# 01_-_ST-LINK_V2_1.net
KiCad netlist of a schematic drawn in Altium Designer
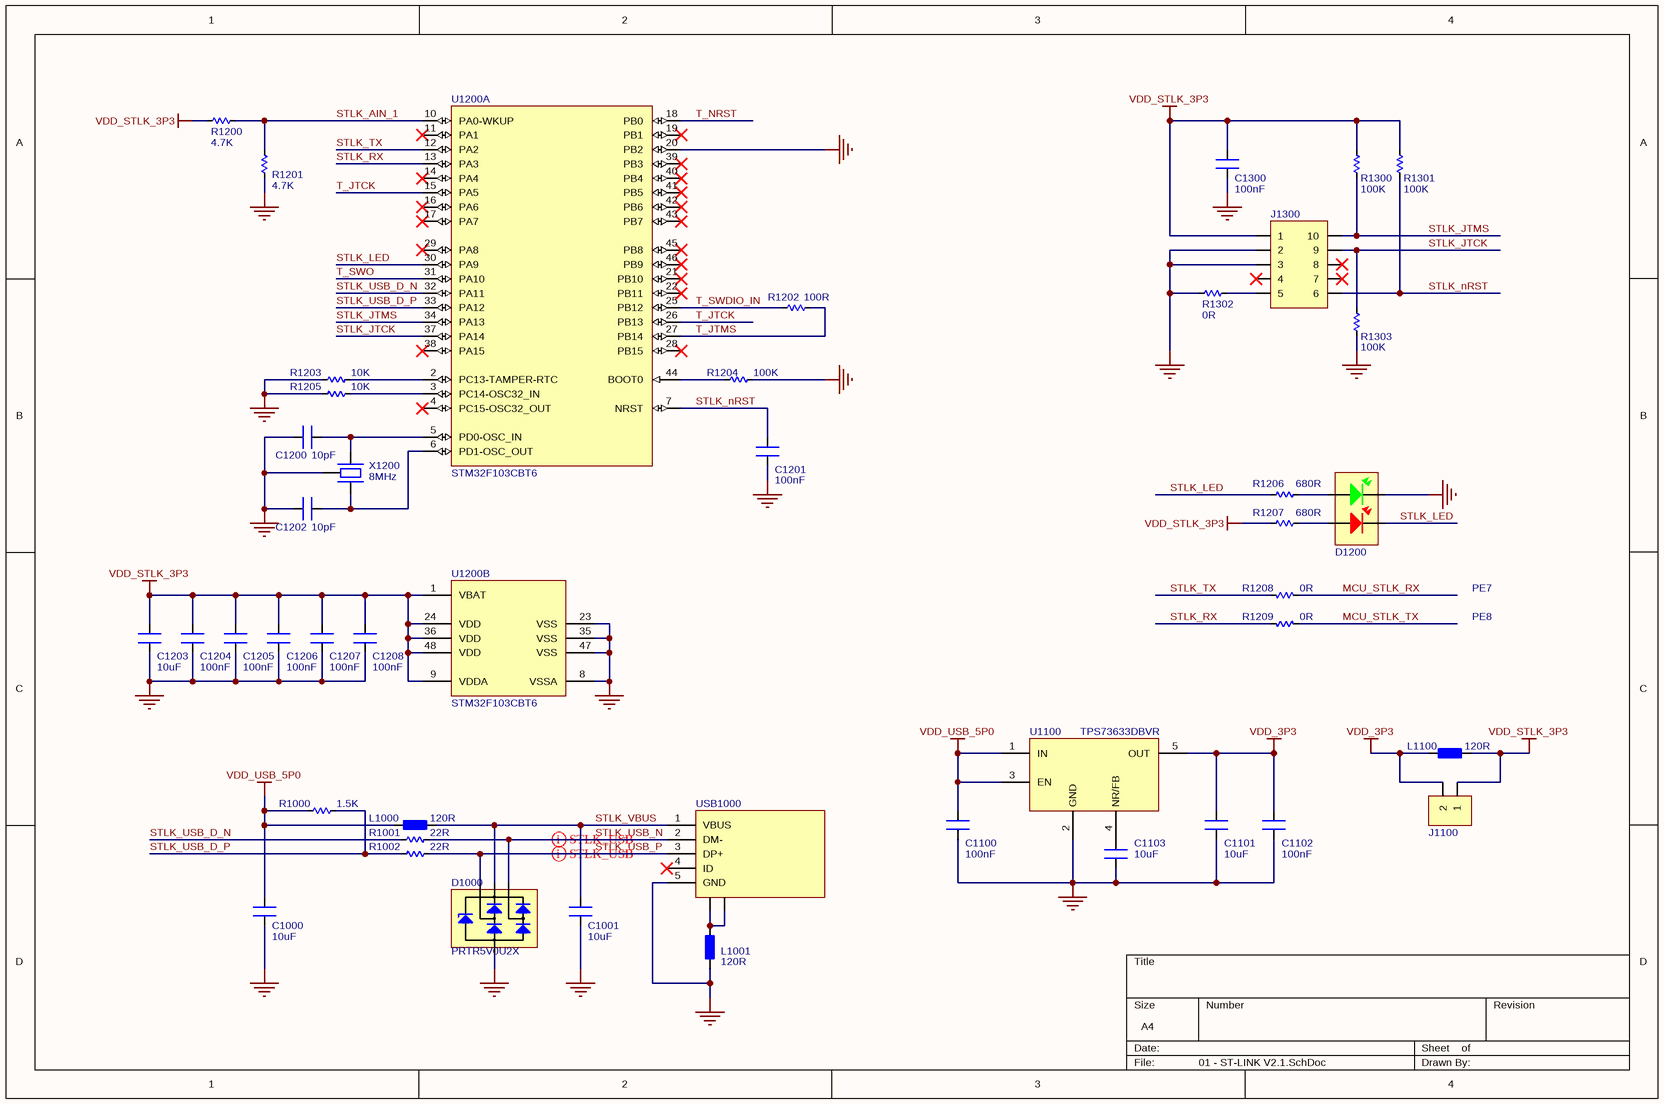
[diagram p0: 01 - ST-LINK V2.1.SchDoc]

(export (version "E")
  (design (tool "Eeschema 10.0.6"))
  (components
    (comp (ref "C1000")
      (value "10uF")
      (footprint "CN-SMD-0603")
      (description "Ceramic Capacitor SMD 0603 10uF ±20% 10V")
      (fields (field (name "Comment") "Capacitor"))
      (libsource (lib "AS50") (part "Cap"))
    )
    (comp (ref "C1001")
      (value "10uF")
      (footprint "CN-SMD-0603")
      (description "Ceramic Capacitor SMD 0603 10uF ±20% 10V")
      (fields (field (name "Comment") "Capacitor"))
      (libsource (lib "AS50") (part "Cap"))
    )
    (comp (ref "C1100")
      (value "100nF")
      (footprint "CN-SMD-0603")
      (description "Ceramic Capacitor SMD 0603 100nF ±20% 50V")
      (fields (field (name "Comment") "Capacitor"))
      (libsource (lib "AS50") (part "Cap"))
    )
    (comp (ref "C1101")
      (value "10uF")
      (footprint "CN-SMD-0603")
      (description "Ceramic Capacitor SMD 0603 10uF ±20% 10V")
      (fields (field (name "Comment") "Capacitor"))
      (libsource (lib "AS50") (part "Cap"))
    )
    (comp (ref "C1102")
      (value "100nF")
      (footprint "CN-SMD-0603")
      (description "Ceramic Capacitor SMD 0603 100nF ±20% 50V")
      (fields (field (name "Comment") "Capacitor"))
      (libsource (lib "AS50") (part "Cap"))
    )
    (comp (ref "C1103")
      (value "10uF")
      (footprint "CN-SMD-0603")
      (description "Ceramic Capacitor SMD 0603 10uF ±20% 10V")
      (fields (field (name "Comment") "Capacitor"))
      (libsource (lib "AS50") (part "Cap"))
    )
    (comp (ref "C1200")
      (value "10pF")
      (footprint "CN-SMD-0402")
      (description "Ceramic Capacitor SMD 0402 10pF ±20% 50V")
      (fields (field (name "Comment") "Capacitor"))
      (libsource (lib "AS50") (part "Cap"))
    )
    (comp (ref "C1201")
      (value "100nF")
      (footprint "CN-SMD-0402")
      (description "Ceramic Capacitor SMD 0402 100nF ±20% 16V")
      (fields (field (name "Comment") "Capacitor"))
      (libsource (lib "AS50") (part "Cap"))
    )
    (comp (ref "C1202")
      (value "10pF")
      (footprint "CN-SMD-0402")
      (description "Ceramic Capacitor SMD 0402 10pF ±20% 50V")
      (fields (field (name "Comment") "Capacitor"))
      (libsource (lib "AS50") (part "Cap"))
    )
    (comp (ref "C1203")
      (value "10uF")
      (footprint "CN-SMD-0603")
      (description "Ceramic Capacitor SMD 0603 10uF ±20% 10V")
      (fields (field (name "Comment") "Capacitor"))
      (libsource (lib "AS50") (part "Cap"))
    )
    (comp (ref "C1204")
      (value "100nF")
      (footprint "CN-SMD-0402")
      (description "Ceramic Capacitor SMD 0402 100nF ±20% 16V")
      (fields (field (name "Comment") "Capacitor"))
      (libsource (lib "AS50") (part "Cap"))
    )
    (comp (ref "C1205")
      (value "100nF")
      (footprint "CN-SMD-0402")
      (description "Ceramic Capacitor SMD 0402 100nF ±20% 16V")
      (fields (field (name "Comment") "Capacitor"))
      (libsource (lib "AS50") (part "Cap"))
    )
    (comp (ref "C1206")
      (value "100nF")
      (footprint "CN-SMD-0402")
      (description "Ceramic Capacitor SMD 0402 100nF ±20% 16V")
      (fields (field (name "Comment") "Capacitor"))
      (libsource (lib "AS50") (part "Cap"))
    )
    (comp (ref "C1207")
      (value "100nF")
      (footprint "CN-SMD-0402")
      (description "Ceramic Capacitor SMD 0402 100nF ±20% 16V")
      (fields (field (name "Comment") "Capacitor"))
      (libsource (lib "AS50") (part "Cap"))
    )
    (comp (ref "C1208")
      (value "100nF")
      (footprint "CN-SMD-0402")
      (description "Ceramic Capacitor SMD 0402 100nF ±20% 16V")
      (fields (field (name "Comment") "Capacitor"))
      (libsource (lib "AS50") (part "Cap"))
    )
    (comp (ref "C1300")
      (value "100nF")
      (footprint "CN-SMD-0402")
      (description "Ceramic Capacitor SMD 0402 100nF ±20% 16V")
      (fields (field (name "Comment") "Capacitor"))
      (libsource (lib "AS50") (part "Cap"))
    )
    (comp (ref "D1000")
      (value "PRTR5V0U2X")
      (footprint "SOT-143")
      (description "Ultra low capacitance double rail-to-rail ESD protection diode")
      (libsource (lib "AS50") (part "PRTR5V0U2X"))
    )
    (comp (ref "D1200")
      (value "LED")
      (footprint "LED-SMD-1615M-RG")
      (description "LED bicolor red green SMD-1615")
      (libsource (lib "AS50") (part "LED RG"))
    )
    (comp (ref "J1100")
      (value "JP2")
      (footprint "JP2-D1T")
      (description "Single 2-pin jumper")
      (libsource (lib "AS50") (part "JP2"))
    )
    (comp (ref "J1300")
      (value "Terminal strip")
      (footprint "JP1.27-10P")
      (description "Terminal strip 5-pin 2-row pitch 0.05\" (1.27mm) SMD straight")
      (libsource (lib "AS50") (part "JP5x2"))
    )
    (comp (ref "L1000")
      (value "120R")
      (footprint "L-SMD-0603")
      (description "Ferrite bead SMD 0603 120 Ohm @100MHz")
      (fields (field (name "Comment") "Ferrite bead"))
      (libsource (lib "AS50") (part "Ferrite bead"))
    )
    (comp (ref "L1001")
      (value "120R")
      (footprint "L-SMD-0603")
      (description "Ferrite bead SMD 0603 120 Ohm @100MHz")
      (fields (field (name "Comment") "Ferrite bead"))
      (libsource (lib "AS50") (part "Ferrite bead"))
    )
    (comp (ref "L1100")
      (value "120R")
      (footprint "L-SMD-0402")
      (description "Ferrite bead SMD 0402 120 Ohm @100MHz")
      (fields (field (name "Comment") "Ferrite bead"))
      (libsource (lib "AS50") (part "Ferrite bead"))
    )
    (comp (ref "R1000")
      (value "1.5K")
      (footprint "RES-SMD-0402")
      (description "Resistor SMD 0402 1.5K 1% 0.063W")
      (fields (field (name "Comment") "Resistor"))
      (libsource (lib "AS50") (part "Res"))
    )
    (comp (ref "R1001")
      (value "22R")
      (footprint "RES-SMD-0402")
      (description "Resistor SMD 0402 22R 1% 0.063W")
      (fields (field (name "Comment") "Resistor"))
      (libsource (lib "AS50") (part "Res"))
    )
    (comp (ref "R1002")
      (value "22R")
      (footprint "RES-SMD-0402")
      (description "Resistor SMD 0402 22R 1% 0.063W")
      (fields (field (name "Comment") "Resistor"))
      (libsource (lib "AS50") (part "Res"))
    )
    (comp (ref "R1200")
      (value "4.7K")
      (footprint "RES-SMD-0402")
      (description "Resistor SMD 0402 4.7K 1% 0.063W")
      (fields (field (name "Comment") "Resistor"))
      (libsource (lib "AS50") (part "Res"))
    )
    (comp (ref "R1201")
      (value "4.7K")
      (footprint "RES-SMD-0402")
      (description "Resistor SMD 0402 4.7K 1% 0.063W")
      (fields (field (name "Comment") "Resistor"))
      (libsource (lib "AS50") (part "Res"))
    )
    (comp (ref "R1202")
      (value "100R")
      (footprint "RES-SMD-0402")
      (description "Resistor SMD 0402 100R 1% 0.063W")
      (fields (field (name "Comment") "Resistor"))
      (libsource (lib "AS50") (part "Res"))
    )
    (comp (ref "R1203")
      (value "10K")
      (footprint "RES-SMD-0402")
      (description "Resistor SMD 0402 10K 1% 0.063W")
      (fields (field (name "Comment") "Resistor"))
      (libsource (lib "AS50") (part "Res"))
    )
    (comp (ref "R1204")
      (value "100K")
      (footprint "RES-SMD-0402")
      (description "Resistor SMD 0402 100K 1% 0.063W")
      (fields (field (name "Comment") "Resistor"))
      (libsource (lib "AS50") (part "Res"))
    )
    (comp (ref "R1205")
      (value "10K")
      (footprint "RES-SMD-0402")
      (description "Resistor SMD 0402 10K 1% 0.063W")
      (fields (field (name "Comment") "Resistor"))
      (libsource (lib "AS50") (part "Res"))
    )
    (comp (ref "R1206")
      (value "680R")
      (footprint "RES-SMD-0402")
      (description "Resistor SMD 0402 680R 1% 0.063W")
      (fields (field (name "Comment") "Resistor"))
      (libsource (lib "AS50") (part "Res"))
    )
    (comp (ref "R1207")
      (value "680R")
      (footprint "RES-SMD-0402")
      (description "Resistor SMD 0402 680R 1% 0.063W")
      (fields (field (name "Comment") "Resistor"))
      (libsource (lib "AS50") (part "Res"))
    )
    (comp (ref "R1208")
      (value "0R")
      (footprint "RES-SMD-0402")
      (description "Resistor SMD 0402 0R 1% 0.063W")
      (fields (field (name "Comment") "Resistor"))
      (libsource (lib "AS50") (part "Res"))
    )
    (comp (ref "R1209")
      (value "0R")
      (footprint "RES-SMD-0402")
      (description "Resistor SMD 0402 0R 1% 0.063W")
      (fields (field (name "Comment") "Resistor"))
      (libsource (lib "AS50") (part "Res"))
    )
    (comp (ref "R1300")
      (value "100K")
      (footprint "RES-SMD-0402")
      (description "Resistor SMD 0402 100K 1% 0.063W")
      (fields (field (name "Comment") "Resistor"))
      (libsource (lib "AS50") (part "Res"))
    )
    (comp (ref "R1301")
      (value "100K")
      (footprint "RES-SMD-0402")
      (description "Resistor SMD 0402 100K 1% 0.063W")
      (fields (field (name "Comment") "Resistor"))
      (libsource (lib "AS50") (part "Res"))
    )
    (comp (ref "R1302")
      (value "0R")
      (footprint "RES-SMD-0402")
      (description "Resistor SMD 0402 0R 1% 0.063W")
      (fields (field (name "Comment") "Resistor"))
      (libsource (lib "AS50") (part "Res"))
    )
    (comp (ref "R1303")
      (value "100K")
      (footprint "RES-SMD-0402")
      (description "Resistor SMD 0402 100K 1% 0.063W")
      (fields (field (name "Comment") "Resistor"))
      (libsource (lib "AS50") (part "Res"))
    )
    (comp (ref "U1100")
      (value "TPS73633DBVR")
      (footprint "SOT-23-5")
      (description "Cap-Free, NMOS, 400-mA Low-Dropout Regulator with Reverse Current Protection")
      (libsource (lib "AS50") (part "TPS73633DBVR"))
    )
    (comp (ref "U1200")
      (value "STM32F103CBT6")
      (footprint "LQFP50P900X900X160-48N")
      (libsource (lib "AS50") (part "STM32F103CBT6"))
    )
    (comp (ref "USB1000")
      (value "USB")
      (footprint "USB_micro-B_F_SMD-2")
      (description "USB female SMD micro-B type")
      (libsource (lib "AS50") (part "USB-5"))
    )
    (comp (ref "X1200")
      (value "Crystal")
      (footprint "XT-SMD-3213M-3P")
      (description "Crystal Oscillator SMD-3123 8MHz 3-pin")
      (fields (field (name "FREQUENCY") "8MHz"))
      (libsource (lib "AS50") (part "XT3"))
    )
  )
  (nets
    (net (code "1") (name "/MCU_STLK_RX") (class "Default")
      (node (ref "R1208") (pin "1") (pinfunction "1_1") (pintype "passive"))
    )
    (net (code "2") (name "/MCU_STLK_TX") (class "Default")
      (node (ref "R1209") (pin "1") (pinfunction "1_1") (pintype "passive"))
    )
    (net (code "3") (name "/STLK_AIN_1") (class "Default")
      (node (ref "R1200") (pin "1") (pinfunction "1_1") (pintype "passive"))
      (node (ref "R1201") (pin "1") (pinfunction "1_1") (pintype "passive"))
      (node (ref "U1200") (pin "10") (pinfunction "PA0-WKUP_10") (pintype "bidirectional"))
    )
    (net (code "4") (name "/STLK_JTCK") (class "Default")
      (node (ref "J1300") (pin "9") (pinfunction "9_9") (pintype "passive"))
      (node (ref "R1303") (pin "1") (pinfunction "1_1") (pintype "passive"))
      (node (ref "U1200") (pin "37") (pinfunction "PA14_37") (pintype "bidirectional"))
    )
    (net (code "5") (name "/STLK_JTMS") (class "Default")
      (node (ref "J1300") (pin "10") (pinfunction "10_10") (pintype "passive"))
      (node (ref "R1300") (pin "2") (pinfunction "2_2") (pintype "passive"))
      (node (ref "U1200") (pin "34") (pinfunction "PA13_34") (pintype "bidirectional"))
    )
    (net (code "6") (name "/STLK_LED") (class "Default")
      (node (ref "D1200") (pin "1") (pinfunction "RED_CN_1") (pintype "passive"))
      (node (ref "R1206") (pin "2") (pinfunction "2_2") (pintype "passive"))
      (node (ref "U1200") (pin "30") (pinfunction "PA9_30") (pintype "bidirectional"))
    )
    (net (code "7") (name "/STLK_RX") (class "Default")
      (node (ref "R1209") (pin "2") (pinfunction "2_2") (pintype "passive"))
      (node (ref "U1200") (pin "13") (pinfunction "PA3_13") (pintype "bidirectional"))
    )
    (net (code "8") (name "/STLK_TX") (class "Default")
      (node (ref "R1208") (pin "2") (pinfunction "2_2") (pintype "passive"))
      (node (ref "U1200") (pin "12") (pinfunction "PA2_12") (pintype "bidirectional"))
    )
    (net (code "9") (name "/STLK_USB_D_N") (class "Default")
      (node (ref "R1001") (pin "2") (pinfunction "2_2") (pintype "passive"))
      (node (ref "U1200") (pin "32") (pinfunction "PA11_32") (pintype "bidirectional"))
    )
    (net (code "10") (name "/STLK_USB_D_P") (class "Default")
      (node (ref "R1000") (pin "1") (pinfunction "1_1") (pintype "passive"))
      (node (ref "R1002") (pin "2") (pinfunction "2_2") (pintype "passive"))
      (node (ref "U1200") (pin "33") (pinfunction "PA12_33") (pintype "bidirectional"))
    )
    (net (code "11") (name "/STLK_USB_N") (class "Default")
      (node (ref "D1000") (pin "3") (pintype "passive"))
      (node (ref "R1001") (pin "1") (pinfunction "1_1") (pintype "passive"))
      (node (ref "USB1000") (pin "2") (pinfunction "DM-_2") (pintype "passive"))
    )
    (net (code "12") (name "/STLK_USB_P") (class "Default")
      (node (ref "D1000") (pin "2") (pintype "passive"))
      (node (ref "R1002") (pin "1") (pinfunction "1_1") (pintype "passive"))
      (node (ref "USB1000") (pin "3") (pinfunction "DP+_3") (pintype "passive"))
    )
    (net (code "13") (name "/STLK_VBUS") (class "Default")
      (node (ref "C1001") (pin "2") (pinfunction "2_2") (pintype "passive"))
      (node (ref "D1000") (pin "4") (pinfunction "VDD_4") (pintype "passive"))
      (node (ref "L1000") (pin "1") (pinfunction "1_1") (pintype "passive"))
      (node (ref "USB1000") (pin "1") (pinfunction "VBUS_1") (pintype "passive"))
    )
    (net (code "14") (name "/STLK_nRST") (class "Default")
      (node (ref "C1201") (pin "2") (pinfunction "2_2") (pintype "passive"))
      (node (ref "J1300") (pin "6") (pinfunction "6_6") (pintype "passive"))
      (node (ref "R1301") (pin "2") (pinfunction "2_2") (pintype "passive"))
      (node (ref "U1200") (pin "7") (pinfunction "NRST_7") (pintype "bidirectional"))
    )
    (net (code "15") (name "/T_JTCK") (class "Default")
      (node (ref "U1200") (pin "15") (pinfunction "PA5_15") (pintype "bidirectional"))
      (node (ref "U1200") (pin "26") (pinfunction "PB13_26") (pintype "bidirectional"))
    )
    (net (code "16") (name "/T_JTMS") (class "Default")
      (node (ref "R1202") (pin "1") (pinfunction "1_1") (pintype "passive"))
      (node (ref "U1200") (pin "27") (pinfunction "PB14_27") (pintype "bidirectional"))
    )
    (net (code "17") (name "/T_NRST") (class "Default")
      (node (ref "U1200") (pin "18") (pinfunction "PB0_18") (pintype "bidirectional"))
    )
    (net (code "18") (name "/T_SWDIO_IN") (class "Default")
      (node (ref "R1202") (pin "2") (pinfunction "2_2") (pintype "passive"))
      (node (ref "U1200") (pin "25") (pinfunction "PB12_25") (pintype "bidirectional"))
    )
    (net (code "19") (name "/T_SWO") (class "Default")
      (node (ref "U1200") (pin "31") (pinfunction "PA10_31") (pintype "bidirectional"))
    )
    (net (code "20") (name "GND") (class "Default")
      (node (ref "C1000") (pin "1") (pinfunction "1_1") (pintype "passive"))
      (node (ref "C1001") (pin "1") (pinfunction "1_1") (pintype "passive"))
      (node (ref "C1100") (pin "1") (pinfunction "1_1") (pintype "passive"))
      (node (ref "C1101") (pin "1") (pinfunction "1_1") (pintype "passive"))
      (node (ref "C1102") (pin "1") (pinfunction "1_1") (pintype "passive"))
      (node (ref "C1103") (pin "1") (pinfunction "1_1") (pintype "passive"))
      (node (ref "C1200") (pin "2") (pinfunction "2_2") (pintype "passive"))
      (node (ref "C1201") (pin "1") (pinfunction "1_1") (pintype "passive"))
      (node (ref "C1202") (pin "2") (pinfunction "2_2") (pintype "passive"))
      (node (ref "C1203") (pin "1") (pinfunction "1_1") (pintype "passive"))
      (node (ref "C1204") (pin "1") (pinfunction "1_1") (pintype "passive"))
      (node (ref "C1205") (pin "1") (pinfunction "1_1") (pintype "passive"))
      (node (ref "C1206") (pin "1") (pinfunction "1_1") (pintype "passive"))
      (node (ref "C1207") (pin "1") (pinfunction "1_1") (pintype "passive"))
      (node (ref "C1208") (pin "1") (pinfunction "1_1") (pintype "passive"))
      (node (ref "C1300") (pin "1") (pinfunction "1_1") (pintype "passive"))
      (node (ref "D1000") (pin "1") (pinfunction "GND_1") (pintype "passive"))
      (node (ref "D1200") (pin "2") (pinfunction "GREEN_CN_2") (pintype "passive"))
      (node (ref "J1300") (pin "2") (pinfunction "2_2") (pintype "passive"))
      (node (ref "J1300") (pin "3") (pinfunction "3_3") (pintype "passive"))
      (node (ref "L1001") (pin "1") (pinfunction "1_1") (pintype "passive"))
      (node (ref "R1201") (pin "2") (pinfunction "2_2") (pintype "passive"))
      (node (ref "R1203") (pin "2") (pinfunction "2_2") (pintype "passive"))
      (node (ref "R1204") (pin "1") (pinfunction "1_1") (pintype "passive"))
      (node (ref "R1205") (pin "2") (pinfunction "2_2") (pintype "passive"))
      (node (ref "R1302") (pin "2") (pinfunction "2_2") (pintype "passive"))
      (node (ref "R1303") (pin "2") (pinfunction "2_2") (pintype "passive"))
      (node (ref "U1100") (pin "2") (pinfunction "GND_2") (pintype "power_in"))
      (node (ref "U1200") (pin "20") (pinfunction "PB2_20") (pintype "bidirectional"))
      (node (ref "U1200") (pin "23") (pinfunction "VSS_23") (pintype "power_in"))
      (node (ref "U1200") (pin "35") (pinfunction "VSS_35") (pintype "power_in"))
      (node (ref "U1200") (pin "47") (pinfunction "VSS_47") (pintype "power_in"))
      (node (ref "U1200") (pin "8") (pinfunction "VSSA_8") (pintype "power_in"))
      (node (ref "USB1000") (pin "5") (pinfunction "GND_5") (pintype "passive"))
      (node (ref "X1200") (pin "3") (pinfunction "3_3") (pintype "passive"))
    )
    (net (code "21") (name "Net-(D1200-GREEN_AN)") (class "Default")
      (node (ref "D1200") (pin "3") (pinfunction "GREEN_AN_3") (pintype "passive"))
      (node (ref "R1206") (pin "1") (pinfunction "1_1") (pintype "passive"))
    )
    (net (code "22") (name "Net-(D1200-RED_AN)") (class "Default")
      (node (ref "D1200") (pin "4") (pinfunction "RED_AN_4") (pintype "passive"))
      (node (ref "R1207") (pin "1") (pinfunction "1_1") (pintype "passive"))
    )
    (net (code "23") (name "Net-(J1300-Pad5)") (class "Default")
      (node (ref "J1300") (pin "5") (pinfunction "5_5") (pintype "passive"))
      (node (ref "R1302") (pin "1") (pinfunction "1_1") (pintype "passive"))
    )
    (net (code "24") (name "Net-(L1001-Pad2)") (class "Default")
      (node (ref "L1001") (pin "2") (pinfunction "2_2") (pintype "passive"))
      (node (ref "USB1000") (pin "0") (pintype "power_in"))
    )
    (net (code "25") (name "Net-(U1100-NR{slash}FB)") (class "Default")
      (node (ref "C1103") (pin "2") (pinfunction "2_2") (pintype "passive"))
      (node (ref "U1100") (pin "4") (pinfunction "NR/FB_4") (pintype "power_in"))
    )
    (net (code "26") (name "Net-(U1200A-BOOT0)") (class "Default")
      (node (ref "R1204") (pin "2") (pinfunction "2_2") (pintype "passive"))
      (node (ref "U1200") (pin "44") (pinfunction "BOOT0_44") (pintype "input"))
    )
    (net (code "27") (name "Net-(U1200A-PC13-TAMPER-RTC)") (class "Default")
      (node (ref "R1203") (pin "1") (pinfunction "1_1") (pintype "passive"))
      (node (ref "U1200") (pin "2") (pinfunction "PC13-TAMPER-RTC_2") (pintype "bidirectional"))
    )
    (net (code "28") (name "Net-(U1200A-PC14-OSC32_IN)") (class "Default")
      (node (ref "R1205") (pin "1") (pinfunction "1_1") (pintype "passive"))
      (node (ref "U1200") (pin "3") (pinfunction "PC14-OSC32_IN_3") (pintype "bidirectional"))
    )
    (net (code "29") (name "Net-(U1200A-PD0-OSC_IN)") (class "Default")
      (node (ref "C1200") (pin "1") (pinfunction "1_1") (pintype "passive"))
      (node (ref "U1200") (pin "5") (pinfunction "PD0-OSC_IN_5") (pintype "bidirectional"))
      (node (ref "X1200") (pin "1") (pinfunction "1_1") (pintype "passive"))
    )
    (net (code "30") (name "Net-(U1200A-PD1-OSC_OUT)") (class "Default")
      (node (ref "C1202") (pin "1") (pinfunction "1_1") (pintype "passive"))
      (node (ref "U1200") (pin "6") (pinfunction "PD1-OSC_OUT_6") (pintype "bidirectional"))
      (node (ref "X1200") (pin "2") (pinfunction "2_2") (pintype "passive"))
    )
    (net (code "31") (name "VDD_3P3") (class "Default")
      (node (ref "C1101") (pin "2") (pinfunction "2_2") (pintype "passive"))
      (node (ref "C1102") (pin "2") (pinfunction "2_2") (pintype "passive"))
      (node (ref "J1100") (pin "2") (pinfunction "2_2") (pintype "passive"))
      (node (ref "L1100") (pin "2") (pinfunction "2_2") (pintype "passive"))
      (node (ref "U1100") (pin "5") (pinfunction "OUT_5") (pintype "power_in"))
    )
    (net (code "32") (name "VDD_STLK_3P3") (class "Default")
      (node (ref "C1203") (pin "2") (pinfunction "2_2") (pintype "passive"))
      (node (ref "C1204") (pin "2") (pinfunction "2_2") (pintype "passive"))
      (node (ref "C1205") (pin "2") (pinfunction "2_2") (pintype "passive"))
      (node (ref "C1206") (pin "2") (pinfunction "2_2") (pintype "passive"))
      (node (ref "C1207") (pin "2") (pinfunction "2_2") (pintype "passive"))
      (node (ref "C1208") (pin "2") (pinfunction "2_2") (pintype "passive"))
      (node (ref "C1300") (pin "2") (pinfunction "2_2") (pintype "passive"))
      (node (ref "J1100") (pin "1") (pinfunction "1_1") (pintype "passive"))
      (node (ref "J1300") (pin "1") (pinfunction "1_1") (pintype "passive"))
      (node (ref "L1100") (pin "1") (pinfunction "1_1") (pintype "passive"))
      (node (ref "R1200") (pin "2") (pinfunction "2_2") (pintype "passive"))
      (node (ref "R1207") (pin "2") (pinfunction "2_2") (pintype "passive"))
      (node (ref "R1300") (pin "1") (pinfunction "1_1") (pintype "passive"))
      (node (ref "R1301") (pin "1") (pinfunction "1_1") (pintype "passive"))
      (node (ref "U1200") (pin "1") (pinfunction "VBAT_1") (pintype "power_in"))
      (node (ref "U1200") (pin "24") (pinfunction "VDD_24") (pintype "power_in"))
      (node (ref "U1200") (pin "36") (pinfunction "VDD_36") (pintype "power_in"))
      (node (ref "U1200") (pin "48") (pinfunction "VDD_48") (pintype "power_in"))
      (node (ref "U1200") (pin "9") (pinfunction "VDDA_9") (pintype "power_in"))
    )
    (net (code "33") (name "VDD_USB_5P0") (class "Default")
      (node (ref "C1000") (pin "2") (pinfunction "2_2") (pintype "passive"))
      (node (ref "C1100") (pin "2") (pinfunction "2_2") (pintype "passive"))
      (node (ref "L1000") (pin "2") (pinfunction "2_2") (pintype "passive"))
      (node (ref "R1000") (pin "2") (pinfunction "2_2") (pintype "passive"))
      (node (ref "U1100") (pin "1") (pinfunction "IN_1") (pintype "power_in"))
      (node (ref "U1100") (pin "3") (pinfunction "EN_3") (pintype "power_in"))
    )
    (net (code "34") (name "unconnected-(J1300-Pad4)") (class "Default")
      (node (ref "J1300") (pin "4") (pinfunction "4_4") (pintype "passive+no_connect"))
    )
    (net (code "35") (name "unconnected-(J1300-Pad7)") (class "Default")
      (node (ref "J1300") (pin "7") (pinfunction "7_7") (pintype "passive+no_connect"))
    )
    (net (code "36") (name "unconnected-(J1300-Pad8)") (class "Default")
      (node (ref "J1300") (pin "8") (pinfunction "8_8") (pintype "passive+no_connect"))
    )
    (net (code "37") (name "unconnected-(U1200A-PA1-Pad11)") (class "Default")
      (node (ref "U1200") (pin "11") (pinfunction "PA1_11") (pintype "bidirectional+no_connect"))
    )
    (net (code "38") (name "unconnected-(U1200A-PA4-Pad14)") (class "Default")
      (node (ref "U1200") (pin "14") (pinfunction "PA4_14") (pintype "bidirectional+no_connect"))
    )
    (net (code "39") (name "unconnected-(U1200A-PA6-Pad16)") (class "Default")
      (node (ref "U1200") (pin "16") (pinfunction "PA6_16") (pintype "bidirectional+no_connect"))
    )
    (net (code "40") (name "unconnected-(U1200A-PA7-Pad17)") (class "Default")
      (node (ref "U1200") (pin "17") (pinfunction "PA7_17") (pintype "bidirectional+no_connect"))
    )
    (net (code "41") (name "unconnected-(U1200A-PA8-Pad29)") (class "Default")
      (node (ref "U1200") (pin "29") (pinfunction "PA8_29") (pintype "bidirectional+no_connect"))
    )
    (net (code "42") (name "unconnected-(U1200A-PA15-Pad38)") (class "Default")
      (node (ref "U1200") (pin "38") (pinfunction "PA15_38") (pintype "bidirectional+no_connect"))
    )
    (net (code "43") (name "unconnected-(U1200A-PB1-Pad19)") (class "Default")
      (node (ref "U1200") (pin "19") (pinfunction "PB1_19") (pintype "bidirectional+no_connect"))
    )
    (net (code "44") (name "unconnected-(U1200A-PB3-Pad39)") (class "Default")
      (node (ref "U1200") (pin "39") (pinfunction "PB3_39") (pintype "bidirectional+no_connect"))
    )
    (net (code "45") (name "unconnected-(U1200A-PB4-Pad40)") (class "Default")
      (node (ref "U1200") (pin "40") (pinfunction "PB4_40") (pintype "bidirectional+no_connect"))
    )
    (net (code "46") (name "unconnected-(U1200A-PB5-Pad41)") (class "Default")
      (node (ref "U1200") (pin "41") (pinfunction "PB5_41") (pintype "bidirectional+no_connect"))
    )
    (net (code "47") (name "unconnected-(U1200A-PB6-Pad42)") (class "Default")
      (node (ref "U1200") (pin "42") (pinfunction "PB6_42") (pintype "bidirectional+no_connect"))
    )
    (net (code "48") (name "unconnected-(U1200A-PB7-Pad43)") (class "Default")
      (node (ref "U1200") (pin "43") (pinfunction "PB7_43") (pintype "bidirectional+no_connect"))
    )
    (net (code "49") (name "unconnected-(U1200A-PB8-Pad45)") (class "Default")
      (node (ref "U1200") (pin "45") (pinfunction "PB8_45") (pintype "bidirectional+no_connect"))
    )
    (net (code "50") (name "unconnected-(U1200A-PB9-Pad46)") (class "Default")
      (node (ref "U1200") (pin "46") (pinfunction "PB9_46") (pintype "bidirectional+no_connect"))
    )
    (net (code "51") (name "unconnected-(U1200A-PB10-Pad21)") (class "Default")
      (node (ref "U1200") (pin "21") (pinfunction "PB10_21") (pintype "bidirectional+no_connect"))
    )
    (net (code "52") (name "unconnected-(U1200A-PB11-Pad22)") (class "Default")
      (node (ref "U1200") (pin "22") (pinfunction "PB11_22") (pintype "bidirectional+no_connect"))
    )
    (net (code "53") (name "unconnected-(U1200A-PB15-Pad28)") (class "Default")
      (node (ref "U1200") (pin "28") (pinfunction "PB15_28") (pintype "bidirectional+no_connect"))
    )
    (net (code "54") (name "unconnected-(U1200A-PC15-OSC32_OUT-Pad4)") (class "Default")
      (node (ref "U1200") (pin "4") (pinfunction "PC15-OSC32_OUT_4") (pintype "bidirectional+no_connect"))
    )
    (net (code "55") (name "unconnected-(USB1000-ID-Pad4)") (class "Default")
      (node (ref "USB1000") (pin "4") (pinfunction "ID_4") (pintype "passive+no_connect"))
    )
  )
)
